# Temp_Control.net
KiCad netlist of a schematic drawn in EAGLE
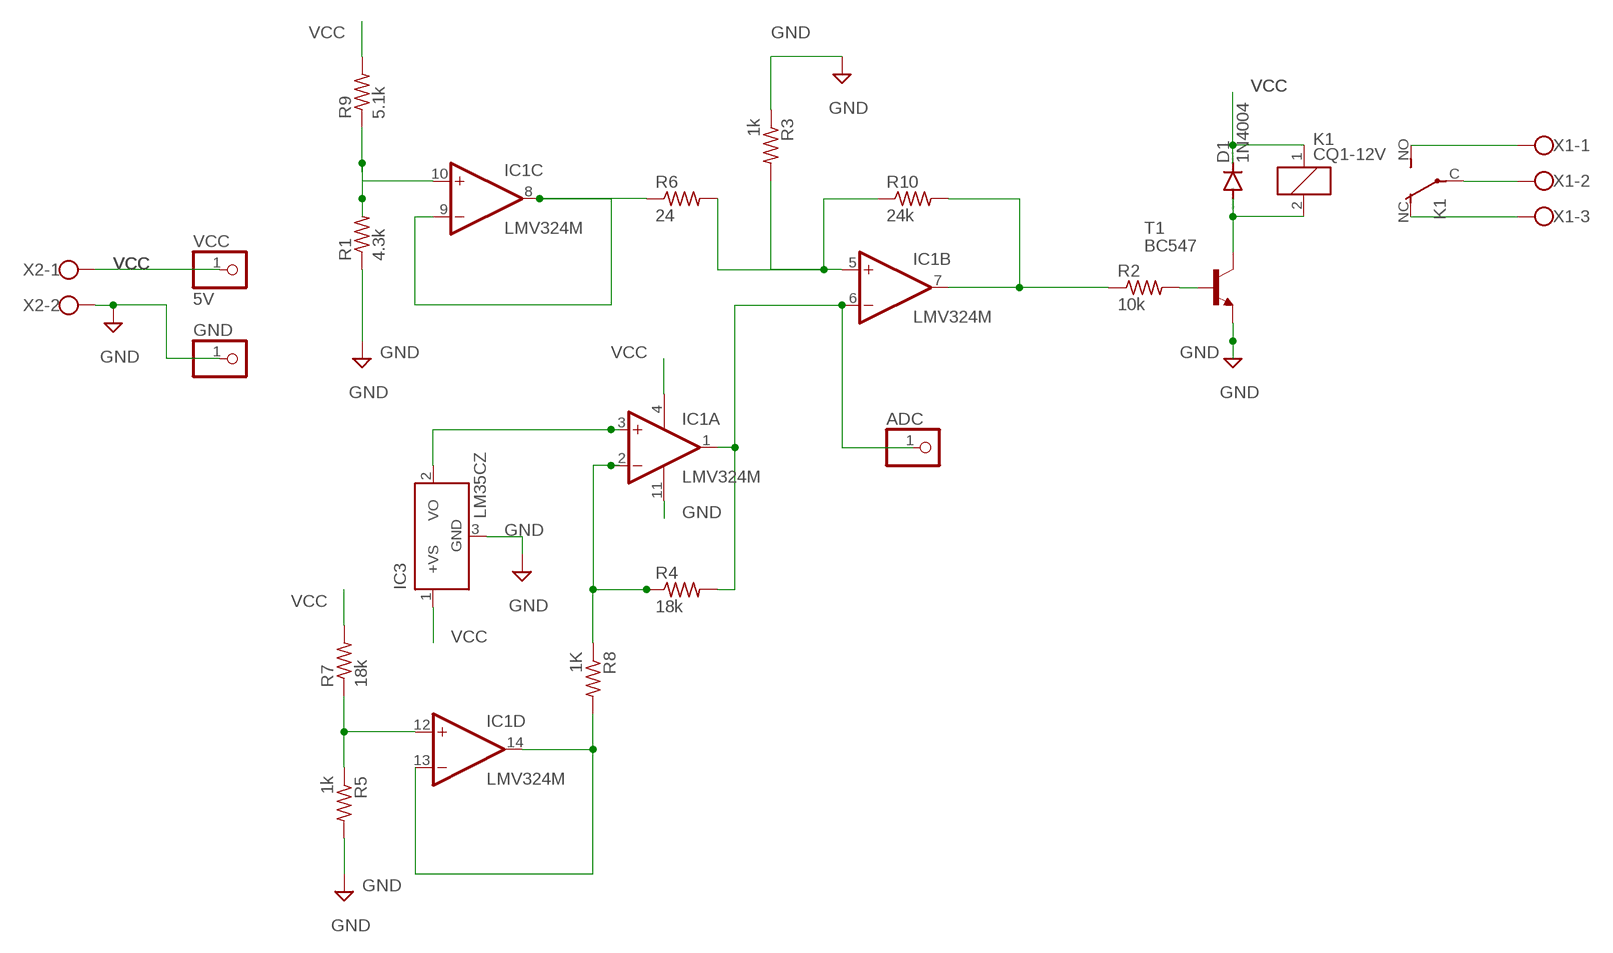
[diagram p0: schematic, sheet 1]

(export (version "E")
  (design (tool "Eeschema 10.0.6"))
  (components
    (comp (ref "ADC")
      (value "PINHD-1X1")
      (footprint "eagle-import:1X01")
      (libsource (lib "eagle-import") (part "PINHD-1X1"))
    )
    (comp (ref "D1")
      (value "1N4004")
      (footprint "eagle-import:DO41-10")
      (libsource (lib "eagle-import") (part "1N4004"))
    )
    (comp (ref "GND")
      (value "PINHD-1X1")
      (footprint "eagle-import:1X01")
      (libsource (lib "eagle-import") (part "PINHD-1X1"))
    )
    (comp (ref "IC1")
      (value "LMV324M")
      (footprint "eagle-import:SO14")
      (libsource (lib "eagle-import") (part "LMV324?M"))
    )
    (comp (ref "IC3")
      (value "LM35CZ")
      (footprint "eagle-import:TO92")
      (libsource (lib "eagle-import") (part "LM35CZ"))
    )
    (comp (ref "K1")
      (value "CQ1-12V")
      (footprint "eagle-import:CQ1")
      (libsource (lib "eagle-import") (part "CQ1-12V"))
    )
    (comp (ref "R1")
      (value "4.3k")
      (footprint "eagle-import:0207_10")
      (libsource (lib "eagle-import") (part "R-US_0207/10"))
    )
    (comp (ref "R2")
      (value "10k")
      (footprint "eagle-import:0207_10")
      (libsource (lib "eagle-import") (part "R-US_0207/10"))
    )
    (comp (ref "R3")
      (value "1k")
      (footprint "eagle-import:0207_10")
      (libsource (lib "eagle-import") (part "R-US_0207/10"))
    )
    (comp (ref "R4")
      (value "18k")
      (footprint "eagle-import:0207_10")
      (libsource (lib "eagle-import") (part "R-US_0207/10"))
    )
    (comp (ref "R5")
      (value "1k")
      (footprint "eagle-import:0207_10")
      (libsource (lib "eagle-import") (part "R-US_0207/10"))
    )
    (comp (ref "R6")
      (value "24")
      (footprint "eagle-import:0207_10")
      (libsource (lib "eagle-import") (part "R-US_0207/10"))
    )
    (comp (ref "R7")
      (value "18k")
      (footprint "eagle-import:0207_10")
      (libsource (lib "eagle-import") (part "R-US_0207/10"))
    )
    (comp (ref "R8")
      (value "1K")
      (footprint "eagle-import:0207_10")
      (libsource (lib "eagle-import") (part "R-US_0207/10"))
    )
    (comp (ref "R9")
      (value "5.1k")
      (footprint "eagle-import:0207_10")
      (libsource (lib "eagle-import") (part "R-US_0207/10"))
    )
    (comp (ref "R10")
      (value "24k")
      (footprint "eagle-import:0207_10")
      (libsource (lib "eagle-import") (part "R-US_0207/10"))
    )
    (comp (ref "T1")
      (value "BC547")
      (footprint "eagle-import:TO92")
      (libsource (lib "eagle-import") (part "BC547"))
    )
    (comp (ref "VCC")
      (value "5V")
      (footprint "eagle-import:1X01")
      (libsource (lib "eagle-import") (part "PINHD-1X1"))
    )
    (comp (ref "X1")
      (value "W237-103")
      (footprint "eagle-import:W237-103")
      (fields (field (name "MPN") "237-103"))
      (libsource (lib "eagle-import") (part "W237-103"))
    )
    (comp (ref "X2")
      (value "W237-102")
      (footprint "eagle-import:W237-102")
      (fields (field (name "MPN") "237-102"))
      (libsource (lib "eagle-import") (part "W237-102"))
    )
  )
  (nets
    (net (code "1") (name "/VCC") (class "Default")
      (node (ref "D1") (pin "C") (pinfunction "C_C") (pintype "passive"))
      (node (ref "IC1") (pin "4") (pinfunction "V+_4") (pintype "power_in"))
      (node (ref "IC3") (pin "1") (pinfunction "+VS_1") (pintype "input"))
      (node (ref "K1") (pin "1") (pinfunction "1_1") (pintype "passive"))
      (node (ref "R7") (pin "2") (pinfunction "2_2") (pintype "passive"))
      (node (ref "R9") (pin "2") (pinfunction "2_2") (pintype "passive"))
      (node (ref "VCC") (pin "1") (pinfunction "1_1") (pintype "passive"))
      (node (ref "X2") (pin "1") (pinfunction "KL_1") (pintype "passive"))
    )
    (net (code "2") (name "GND") (class "Default")
      (node (ref "GND") (pin "1") (pinfunction "1_1") (pintype "passive"))
      (node (ref "IC1") (pin "11") (pinfunction "V-_11") (pintype "power_in"))
      (node (ref "IC3") (pin "3") (pinfunction "GND_3") (pintype "power_in"))
      (node (ref "R1") (pin "1") (pinfunction "1_1") (pintype "passive"))
      (node (ref "R3") (pin "1") (pinfunction "1_1") (pintype "passive"))
      (node (ref "R5") (pin "2") (pinfunction "2_2") (pintype "passive"))
      (node (ref "T1") (pin "1") (pinfunction "E_1") (pintype "passive"))
      (node (ref "X2") (pin "2") (pinfunction "KL_2") (pintype "passive"))
    )
    (net (code "3") (name "Net-(IC1A-+IN)") (class "Default")
      (node (ref "IC1") (pin "3") (pinfunction "+IN_3") (pintype "input"))
      (node (ref "IC3") (pin "2") (pinfunction "VO_2") (pintype "input"))
    )
    (net (code "4") (name "Net-(IC1A--IN)") (class "Default")
      (node (ref "IC1") (pin "2") (pinfunction "-IN_2") (pintype "input"))
      (node (ref "R4") (pin "1") (pinfunction "1_1") (pintype "passive"))
      (node (ref "R8") (pin "1") (pinfunction "1_1") (pintype "passive"))
    )
    (net (code "5") (name "Net-(IC1A-OUT)") (class "Default")
      (node (ref "ADC") (pin "1") (pinfunction "1_1") (pintype "passive"))
      (node (ref "IC1") (pin "1") (pinfunction "OUT_1") (pintype "output"))
      (node (ref "IC1") (pin "6") (pinfunction "-IN_6") (pintype "input"))
      (node (ref "R4") (pin "2") (pinfunction "2_2") (pintype "passive"))
    )
    (net (code "6") (name "Net-(IC1B-+IN)") (class "Default")
      (node (ref "IC1") (pin "5") (pinfunction "+IN_5") (pintype "input"))
      (node (ref "R10") (pin "1") (pinfunction "1_1") (pintype "passive"))
      (node (ref "R3") (pin "2") (pinfunction "2_2") (pintype "passive"))
      (node (ref "R6") (pin "2") (pinfunction "2_2") (pintype "passive"))
    )
    (net (code "7") (name "Net-(IC1B-OUT)") (class "Default")
      (node (ref "IC1") (pin "7") (pinfunction "OUT_7") (pintype "output"))
      (node (ref "R10") (pin "2") (pinfunction "2_2") (pintype "passive"))
      (node (ref "R2") (pin "1") (pinfunction "1_1") (pintype "passive"))
    )
    (net (code "8") (name "Net-(IC1C-+IN)") (class "Default")
      (node (ref "IC1") (pin "10") (pinfunction "+IN_10") (pintype "input"))
      (node (ref "R1") (pin "2") (pinfunction "2_2") (pintype "passive"))
      (node (ref "R9") (pin "1") (pinfunction "1_1") (pintype "passive"))
    )
    (net (code "9") (name "Net-(IC1C--IN)") (class "Default")
      (node (ref "IC1") (pin "8") (pinfunction "OUT_8") (pintype "output"))
      (node (ref "IC1") (pin "9") (pinfunction "-IN_9") (pintype "input"))
      (node (ref "R6") (pin "1") (pinfunction "1_1") (pintype "passive"))
    )
    (net (code "10") (name "Net-(IC1D-+IN)") (class "Default")
      (node (ref "IC1") (pin "12") (pinfunction "+IN_12") (pintype "input"))
      (node (ref "R5") (pin "1") (pinfunction "1_1") (pintype "passive"))
      (node (ref "R7") (pin "1") (pinfunction "1_1") (pintype "passive"))
    )
    (net (code "11") (name "Net-(IC1D--IN)") (class "Default")
      (node (ref "IC1") (pin "13") (pinfunction "-IN_13") (pintype "input"))
      (node (ref "IC1") (pin "14") (pinfunction "OUT_14") (pintype "output"))
      (node (ref "R8") (pin "2") (pinfunction "2_2") (pintype "passive"))
    )
    (net (code "12") (name "Net-(K1B-O)") (class "Default")
      (node (ref "K1") (pin "NC") (pinfunction "O_NC") (pintype "passive"))
      (node (ref "X1") (pin "3") (pinfunction "KL_3") (pintype "passive"))
    )
    (net (code "13") (name "Net-(K1B-P)") (class "Default")
      (node (ref "K1") (pin "C") (pinfunction "P_C") (pintype "passive"))
      (node (ref "X1") (pin "2") (pinfunction "KL_2") (pintype "passive"))
    )
    (net (code "14") (name "Net-(K1B-S)") (class "Default")
      (node (ref "K1") (pin "NO") (pinfunction "S_NO") (pintype "passive"))
      (node (ref "X1") (pin "1") (pinfunction "KL_1") (pintype "passive"))
    )
    (net (code "15") (name "Net-(T1-B)") (class "Default")
      (node (ref "R2") (pin "2") (pinfunction "2_2") (pintype "passive"))
      (node (ref "T1") (pin "2") (pinfunction "B_2") (pintype "passive"))
    )
    (net (code "16") (name "Net-(T1-C)") (class "Default")
      (node (ref "D1") (pin "A") (pinfunction "A_A") (pintype "passive"))
      (node (ref "K1") (pin "2") (pinfunction "2_2") (pintype "passive"))
      (node (ref "T1") (pin "3") (pinfunction "C_3") (pintype "passive"))
    )
  )
)
